# PARK_COUNTER_PT1_1.net
KiCad netlist of a schematic drawn in Altium Designer
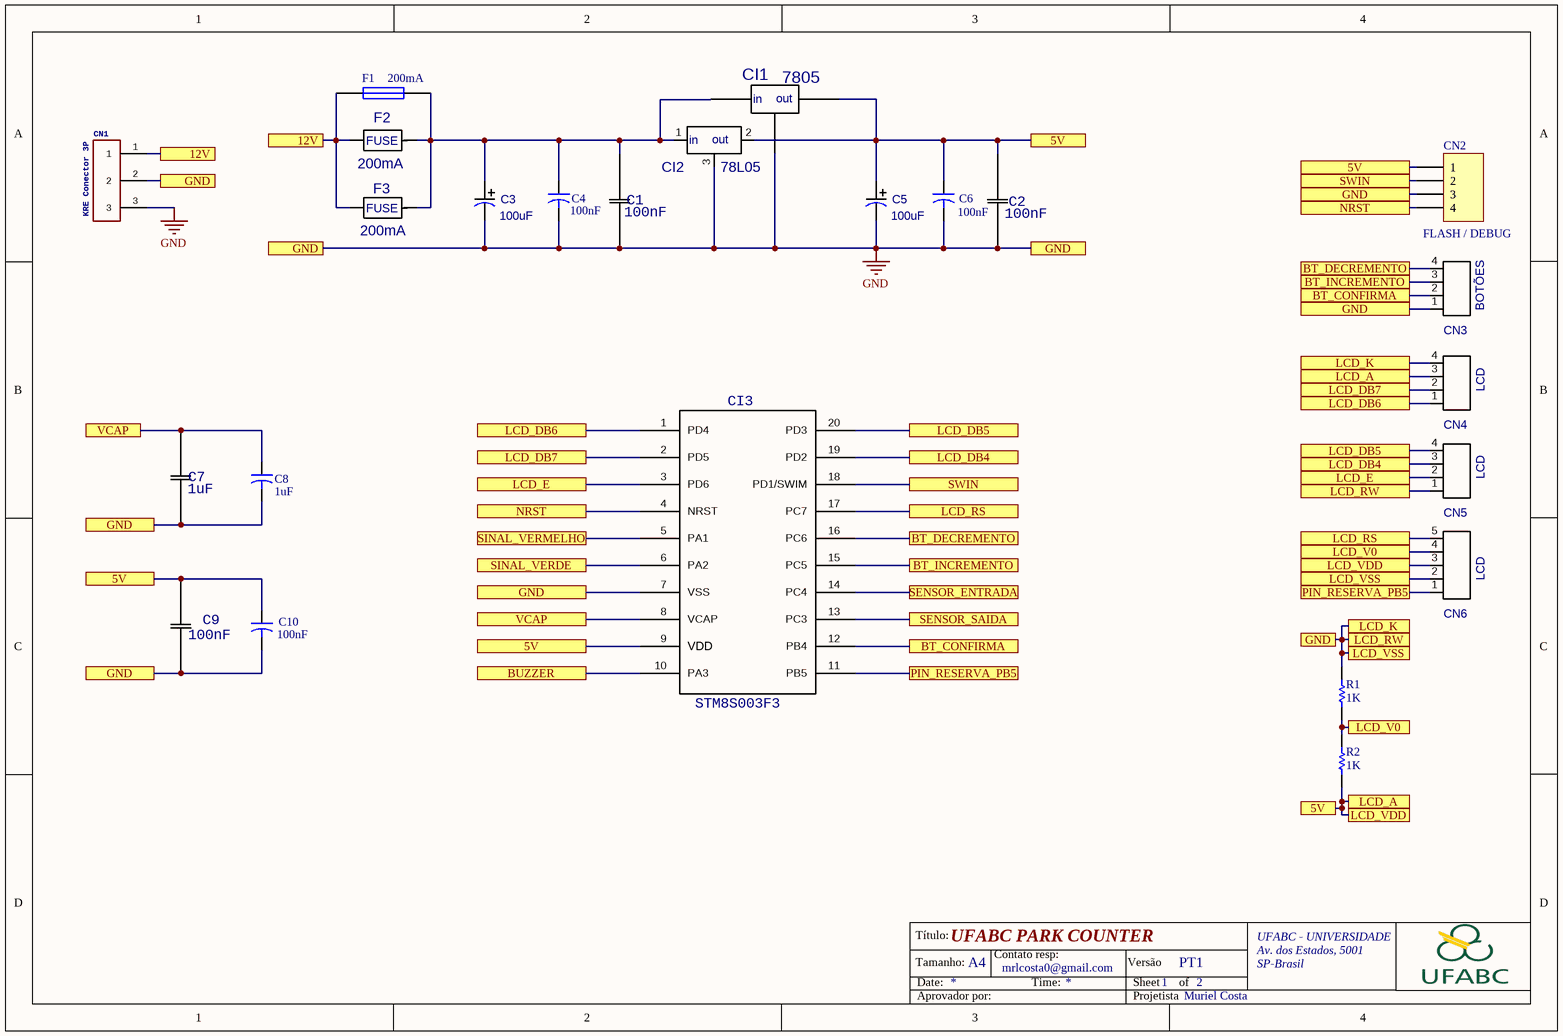
[diagram p0: PARK_COUNTER_PT1_1.SchDoc]

(export (version "E")
  (design (tool "Eeschema 10.0.6"))
  (components
    (comp (ref "C1")
      (value "100nF")
      (footprint "C0603")
      (description "Capacitor")
      (fields (field (name "Comment") "C0603"))
      (libsource (lib "SMD") (part "C0603"))
    )
    (comp (ref "C2")
      (value "100nF")
      (footprint "C0603")
      (description "Capacitor")
      (fields (field (name "Comment") "C0603"))
      (libsource (lib "SMD") (part "C0603"))
    )
    (comp (ref "C3")
      (value "100uF")
      (footprint "C_ELET_D8P5/3.5")
      (fields (field (name "Comment") "C_ELET_D8P5_35"))
      (libsource (lib "PTH") (part "C_ELET_D8P5_35"))
    )
    (comp (ref "C4")
      (value "100nF")
      (footprint "CAPR5-4X5")
      (description "Capacitor")
      (fields (field (name "Comment") "Cap2") (field (name "PUBLISHER") "Altium Limited"))
      (libsource (lib "Miscellaneous Devices") (part "Cap2"))
    )
    (comp (ref "C5")
      (value "100uF")
      (footprint "C_ELET_D8P5/3.5")
      (fields (field (name "Comment") "C_ELET_D8P5_35"))
      (libsource (lib "PTH") (part "C_ELET_D8P5_35"))
    )
    (comp (ref "C6")
      (value "100nF")
      (footprint "CAPR5-4X5")
      (description "Capacitor")
      (fields (field (name "Comment") "Cap2") (field (name "PUBLISHER") "Altium Limited"))
      (libsource (lib "Miscellaneous Devices") (part "Cap2"))
    )
    (comp (ref "C7")
      (value "1uF")
      (footprint "C0603")
      (description "Capacitor")
      (fields (field (name "Comment") "C0603"))
      (libsource (lib "SMD") (part "C0603"))
    )
    (comp (ref "C8")
      (value "1uF")
      (footprint "CAPR5-4X5")
      (description "Capacitor")
      (fields (field (name "Comment") "Cap2") (field (name "PUBLISHER") "Altium Limited"))
      (libsource (lib "Miscellaneous Devices") (part "Cap2"))
    )
    (comp (ref "C9")
      (value "100nF")
      (footprint "C0603")
      (description "Capacitor")
      (fields (field (name "Comment") "C0603"))
      (libsource (lib "SMD") (part "C0603"))
    )
    (comp (ref "C10")
      (value "100nF")
      (footprint "CAPR5-4X5")
      (description "Capacitor")
      (fields (field (name "Comment") "Cap2") (field (name "PUBLISHER") "Altium Limited"))
      (libsource (lib "Miscellaneous Devices") (part "Cap2"))
    )
    (comp (ref "CI1")
      (value "7805")
      (footprint "CI_7805_TO220_V")
      (fields (field (name "PART NUMBER") "004.02.00002"))
      (libsource (lib "PTH") (part "CI_7805_TO220_V"))
    )
    (comp (ref "CI2")
      (value "78L05")
      (footprint "TO92_78L05")
      (description "Glass Zener Diode, 500 Milliwatt")
      (fields (field (name "PART NUMBER") "004.02.00003"))
      (libsource (lib "PTH") (part "CI_78L05_TO92"))
    )
    (comp (ref "CI3")
      (value "STM8S003F3")
      (footprint "TSSOP20")
      (fields (field (name "PART NUMBER") "004.07.00026") (field (name "Comment") "CI_STM8S003F3_TSSOP20"))
      (libsource (lib "SMD") (part "CI_STM8S003F3_TSSOP20"))
    )
    (comp (ref "CN1") (value "KRE Conector 3P") (footprint "KRE-3P") (libsource (lib "kre") (part "KRE-3P")))
    (comp (ref "CN2")
      (value "FLASH / DEBUG")
      (footprint "HDR1X4")
      (description "Header, 4-Pin")
      (fields (field (name "PUBLISHER") "Altium Limited"))
      (libsource (lib "Miscellaneous Connectors") (part "Header 4"))
    )
    (comp (ref "CN3")
      (value "BOTÕES")
      (footprint "CON_BP1X4_180")
      (description "Capacitor")
      (fields (field (name "Comment") "CON_BP1X4_180"))
      (libsource (lib "CONECTORES") (part "CON_BP1X4_180"))
    )
    (comp (ref "CN4")
      (value "LCD")
      (footprint "CON_BP1X4_180")
      (description "Capacitor")
      (fields (field (name "Comment") "CON_BP1X4_180"))
      (libsource (lib "CONECTORES") (part "CON_BP1X4_180"))
    )
    (comp (ref "CN5")
      (value "LCD")
      (footprint "CON_BP1X4_180")
      (description "Capacitor")
      (fields (field (name "Comment") "CON_BP1X4_180"))
      (libsource (lib "CONECTORES") (part "CON_BP1X4_180"))
    )
    (comp (ref "CN6")
      (value "LCD")
      (footprint "CON_BP1X5_180")
      (fields (field (name "Comment") "CON_BP1X5_180"))
      (libsource (lib "CONECTORES") (part "CON_BP1X5_180"))
    )
    (comp (ref "F1")
      (value "200mA")
      (footprint "PIN-W2/E2.8")
      (description "Fuse")
      (fields (field (name "PUBLISHER") "Altium Limited"))
      (libsource (lib "Miscellaneous Devices") (part "Fuse 1"))
    )
    (comp (ref "F2")
      (value "200mA")
      (footprint "MINI_FUSE_BOARD_GLASS")
      (fields (field (name "Comment") "MINI_FUSE_BOARD_GLASS"))
      (libsource (lib "PTH") (part "fuse_board_glass"))
    )
    (comp (ref "F3")
      (value "200mA")
      (footprint "fuse_board_suporte")
      (fields (field (name "Comment") "MINI_FUSE_BOARD_SUP_GLASS"))
      (libsource (lib "PTH") (part "fuse_board_suporte"))
    )
    (comp (ref "R1")
      (value "1K")
      (footprint "AXIAL-0.3")
      (description "Resistor")
      (fields (field (name "Comment") "Res1") (field (name "PUBLISHER") "Altium Limited"))
      (libsource (lib "Miscellaneous Devices") (part "Res1"))
    )
    (comp (ref "R2")
      (value "1K")
      (footprint "AXIAL-0.3")
      (description "Resistor")
      (fields (field (name "Comment") "Res1") (field (name "PUBLISHER") "Altium Limited"))
      (libsource (lib "Miscellaneous Devices") (part "Res1"))
    )
  )
  (nets
    (net (code "1") (name "/5V") (class "Default")
      (node (ref "C10") (pin "1") (pinfunction "1_1") (pintype "passive"))
      (node (ref "C2") (pin "2") (pinfunction "2_2") (pintype "passive"))
      (node (ref "C5") (pin "2") (pinfunction "2_2") (pintype "passive"))
      (node (ref "C6") (pin "1") (pinfunction "1_1") (pintype "passive"))
      (node (ref "C9") (pin "2") (pinfunction "2_2") (pintype "passive"))
      (node (ref "CI1") (pin "2") (pintype "passive"))
      (node (ref "CI2") (pin "2") (pinfunction "out_2") (pintype "passive"))
      (node (ref "CI3") (pin "9") (pinfunction "VDD_9") (pintype "passive"))
      (node (ref "CN2") (pin "1") (pinfunction "1_1") (pintype "passive"))
      (node (ref "CN4") (pin "3") (pintype "passive"))
      (node (ref "CN6") (pin "3") (pintype "passive"))
      (node (ref "R2") (pin "1") (pinfunction "1_1") (pintype "passive"))
    )
    (net (code "2") (name "/12V") (class "Default")
      (node (ref "CN1") (pin "1") (pinfunction "1_1") (pintype "passive"))
      (node (ref "F1") (pin "1") (pinfunction "1_1") (pintype "passive"))
      (node (ref "F2") (pin "2") (pintype "passive"))
      (node (ref "F3") (pin "2") (pintype "passive"))
    )
    (net (code "3") (name "/BT_CONFIRMA") (class "Default")
      (node (ref "CI3") (pin "12") (pinfunction "PB4_12") (pintype "passive"))
      (node (ref "CN3") (pin "2") (pintype "passive"))
    )
    (net (code "4") (name "/BT_DECREMENTO") (class "Default")
      (node (ref "CI3") (pin "16") (pinfunction "PC6_16") (pintype "passive"))
      (node (ref "CN3") (pin "4") (pintype "passive"))
    )
    (net (code "5") (name "/BT_INCREMENTO") (class "Default")
      (node (ref "CI3") (pin "15") (pinfunction "PC5_15") (pintype "passive"))
      (node (ref "CN3") (pin "3") (pintype "passive"))
    )
    (net (code "6") (name "/BUZZER") (class "Default")
      (node (ref "CI3") (pin "10") (pinfunction "PA3_10") (pintype "passive"))
    )
    (net (code "7") (name "/LCD_DB4") (class "Default")
      (node (ref "CI3") (pin "19") (pinfunction "PD2_19") (pintype "passive"))
      (node (ref "CN5") (pin "3") (pintype "passive"))
    )
    (net (code "8") (name "/LCD_DB5") (class "Default")
      (node (ref "CI3") (pin "20") (pinfunction "PD3_20") (pintype "passive"))
      (node (ref "CN5") (pin "4") (pintype "passive"))
    )
    (net (code "9") (name "/LCD_DB6") (class "Default")
      (node (ref "CI3") (pin "1") (pinfunction "PD4_1") (pintype "passive"))
      (node (ref "CN4") (pin "1") (pintype "passive"))
    )
    (net (code "10") (name "/LCD_DB7") (class "Default")
      (node (ref "CI3") (pin "2") (pinfunction "PD5_2") (pintype "passive"))
      (node (ref "CN4") (pin "2") (pintype "passive"))
    )
    (net (code "11") (name "/LCD_E") (class "Default")
      (node (ref "CI3") (pin "3") (pinfunction "PD6_3") (pintype "passive"))
      (node (ref "CN5") (pin "2") (pintype "passive"))
    )
    (net (code "12") (name "/LCD_RS") (class "Default")
      (node (ref "CI3") (pin "17") (pinfunction "PC7_17") (pintype "passive"))
      (node (ref "CN6") (pin "5") (pintype "passive"))
    )
    (net (code "13") (name "/LCD_V0") (class "Default")
      (node (ref "CN6") (pin "4") (pintype "passive"))
      (node (ref "R1") (pin "1") (pinfunction "1_1") (pintype "passive"))
      (node (ref "R2") (pin "2") (pinfunction "2_2") (pintype "passive"))
    )
    (net (code "14") (name "/NRST") (class "Default")
      (node (ref "CI3") (pin "4") (pinfunction "NRST_4") (pintype "passive"))
      (node (ref "CN2") (pin "4") (pinfunction "4_4") (pintype "passive"))
    )
    (net (code "15") (name "/PIN_RESERVA_PB5") (class "Default")
      (node (ref "CI3") (pin "11") (pinfunction "PB5_11") (pintype "passive"))
      (node (ref "CN6") (pin "1") (pintype "passive"))
    )
    (net (code "16") (name "/SENSOR_ENTRADA") (class "Default")
      (node (ref "CI3") (pin "14") (pinfunction "PC4_14") (pintype "passive"))
    )
    (net (code "17") (name "/SENSOR_SAIDA") (class "Default")
      (node (ref "CI3") (pin "13") (pinfunction "PC3_13") (pintype "passive"))
    )
    (net (code "18") (name "/SINAL_VERDE") (class "Default")
      (node (ref "CI3") (pin "6") (pinfunction "PA2_6") (pintype "passive"))
    )
    (net (code "19") (name "/SINAL_VERMELHO") (class "Default")
      (node (ref "CI3") (pin "5") (pinfunction "PA1_5") (pintype "passive"))
    )
    (net (code "20") (name "/SWIN") (class "Default")
      (node (ref "CI3") (pin "18") (pinfunction "PD1/SWIM_18") (pintype "passive"))
      (node (ref "CN2") (pin "2") (pinfunction "2_2") (pintype "passive"))
    )
    (net (code "21") (name "/VCAP") (class "Default")
      (node (ref "C7") (pin "2") (pinfunction "2_2") (pintype "passive"))
      (node (ref "C8") (pin "1") (pinfunction "1_1") (pintype "passive"))
      (node (ref "CI3") (pin "8") (pinfunction "VCAP_8") (pintype "passive"))
    )
    (net (code "22") (name "GND") (class "Default")
      (node (ref "C1") (pin "1") (pinfunction "1_1") (pintype "passive"))
      (node (ref "C10") (pin "2") (pinfunction "2_2") (pintype "passive"))
      (node (ref "C2") (pin "1") (pinfunction "1_1") (pintype "passive"))
      (node (ref "C3") (pin "1") (pinfunction "1_1") (pintype "passive"))
      (node (ref "C4") (pin "2") (pinfunction "2_2") (pintype "passive"))
      (node (ref "C5") (pin "1") (pinfunction "1_1") (pintype "passive"))
      (node (ref "C6") (pin "2") (pinfunction "2_2") (pintype "passive"))
      (node (ref "C7") (pin "1") (pinfunction "1_1") (pintype "passive"))
      (node (ref "C8") (pin "2") (pinfunction "2_2") (pintype "passive"))
      (node (ref "C9") (pin "1") (pinfunction "1_1") (pintype "passive"))
      (node (ref "CI1") (pin "3") (pintype "passive"))
      (node (ref "CI2") (pin "3") (pinfunction "gnd_3") (pintype "passive"))
      (node (ref "CI3") (pin "7") (pinfunction "VSS_7") (pintype "passive"))
      (node (ref "CN1") (pin "2") (pinfunction "2_2") (pintype "passive"))
      (node (ref "CN1") (pin "3") (pinfunction "3_3") (pintype "passive"))
      (node (ref "CN2") (pin "3") (pinfunction "3_3") (pintype "passive"))
      (node (ref "CN3") (pin "1") (pintype "passive"))
      (node (ref "CN4") (pin "4") (pintype "passive"))
      (node (ref "CN5") (pin "1") (pintype "passive"))
      (node (ref "CN6") (pin "2") (pintype "passive"))
      (node (ref "R1") (pin "2") (pinfunction "2_2") (pintype "passive"))
    )
    (net (code "23") (name "Net-(CI2-in)") (class "Default")
      (node (ref "C1") (pin "2") (pinfunction "2_2") (pintype "passive"))
      (node (ref "C3") (pin "2") (pinfunction "2_2") (pintype "passive"))
      (node (ref "C4") (pin "1") (pinfunction "1_1") (pintype "passive"))
      (node (ref "CI1") (pin "1") (pintype "passive"))
      (node (ref "CI2") (pin "1") (pinfunction "in_1") (pintype "passive"))
      (node (ref "F1") (pin "2") (pinfunction "2_2") (pintype "passive"))
      (node (ref "F2") (pin "1") (pintype "passive"))
      (node (ref "F3") (pin "1") (pintype "passive"))
    )
    (net (code "24") (name "unconnected-(C3-Pad3)") (class "Default")
      (node (ref "C3") (pin "3") (pintype "passive"))
    )
    (net (code "25") (name "unconnected-(C5-Pad3)") (class "Default")
      (node (ref "C5") (pin "3") (pintype "passive"))
    )
    (net (code "26") (name "unconnected-(F2-Pad3)") (class "Default")
      (node (ref "F2") (pin "3") (pintype "passive"))
    )
    (net (code "27") (name "unconnected-(F2-Pad4)") (class "Default")
      (node (ref "F2") (pin "4") (pintype "passive"))
    )
    (net (code "28") (name "unconnected-(F3-Pad3)") (class "Default")
      (node (ref "F3") (pin "3") (pintype "passive"))
    )
    (net (code "29") (name "unconnected-(F3-Pad4)") (class "Default")
      (node (ref "F3") (pin "4") (pintype "passive"))
    )
  )
)
